# bqZUM_MCU.net
KiCad netlist of a schematic drawn in Altium Designer
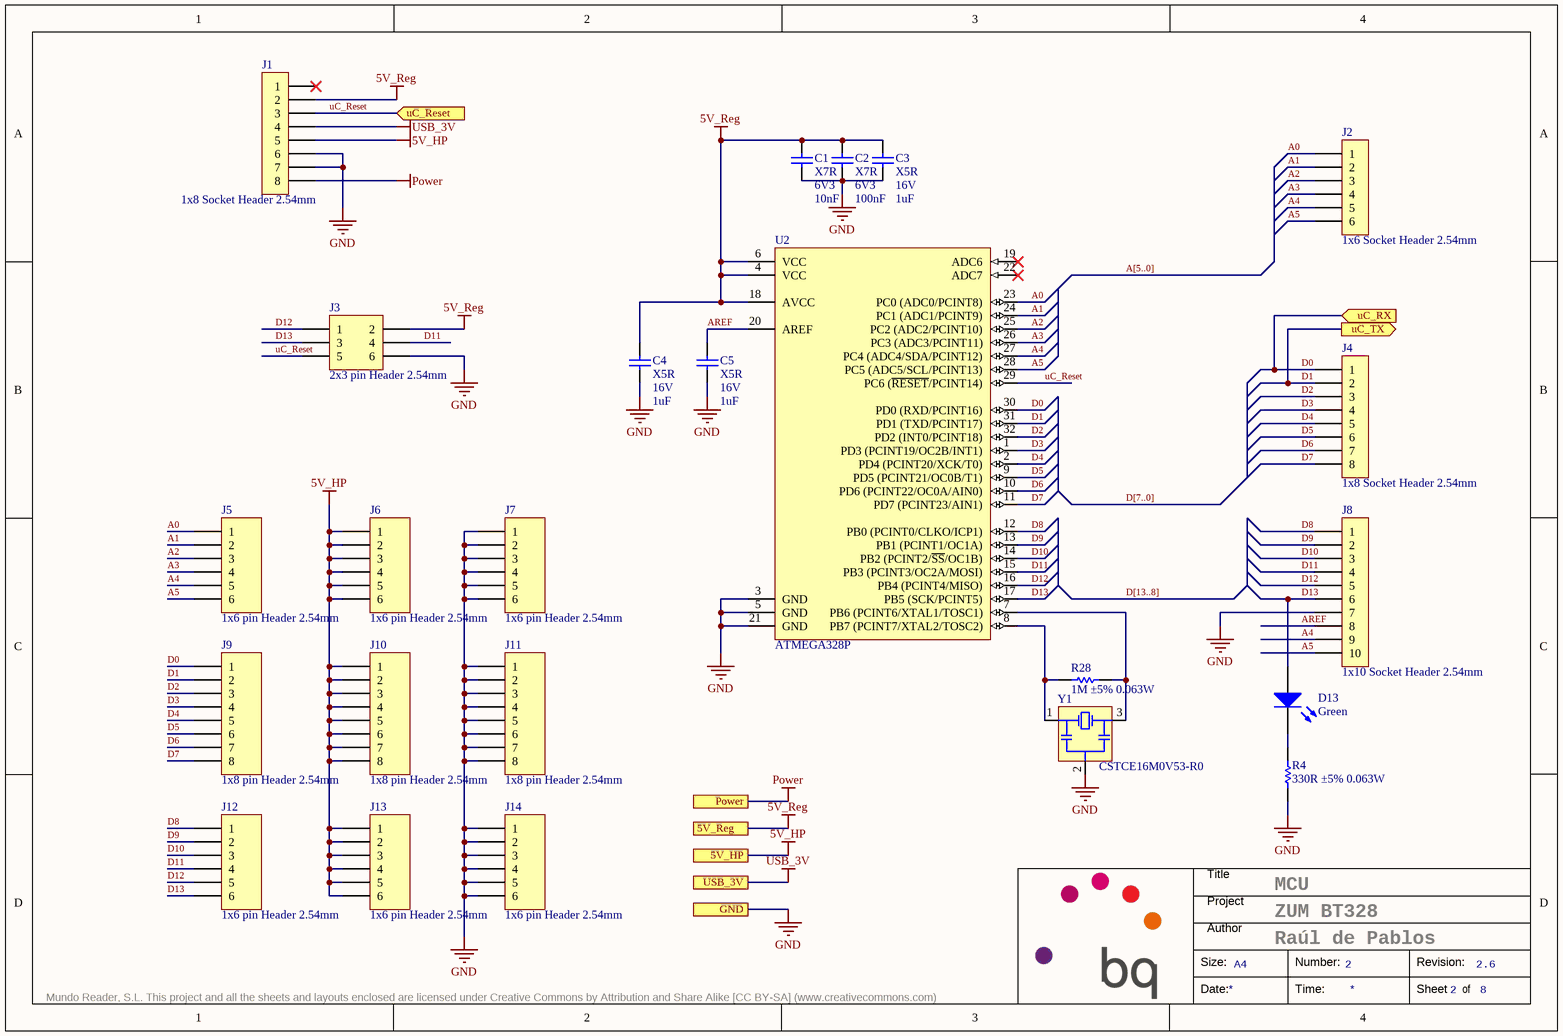
[diagram p0: bqZUM_MCU.SchDoc]

(export (version "E")
  (design (tool "Eeschema 10.0.6"))
  (components
    (comp (ref "C1")
      (value "Capacitor")
      (footprint "C0402")
      (fields
        (field (name "DIELECTRIC") "X7R")
        (field (name "VOLTAGE") "6V3")
        (field (name "CAPACITANCE") "10nF")
        (field (name "PART NUMBER") "C0402_10nF_6V3_±10%")
        (field (name "TOLERANCE") "±10%")
        (field (name "MANUFACTURER") "Kemet")
      )
      (libsource (lib "Pasives_Capacitor_SMD") (part "Capacitor"))
    )
    (comp (ref "C2")
      (value "Capacitor")
      (footprint "C0402")
      (fields
        (field (name "DIELECTRIC") "X7R")
        (field (name "VOLTAGE") "6V3")
        (field (name "CAPACITANCE") "100nF")
        (field (name "PART NUMBER") "C0402_100nF_6V3_±10%")
        (field (name "TOLERANCE") "±10%")
        (field (name "MANUFACTURER") "Kemet")
      )
      (libsource (lib "Pasives_Capacitor_SMD") (part "Capacitor"))
    )
    (comp (ref "C3")
      (value "Capacitor")
      (footprint "C0603")
      (fields
        (field (name "DIELECTRIC") "X5R")
        (field (name "VOLTAGE") "16V")
        (field (name "CAPACITANCE") "1uF")
        (field (name "PART NUMBER") "C0603_1uF_16V_±10%")
        (field (name "TOLERANCE") "±10%")
        (field (name "MANUFACTURER") "Kemet")
      )
      (libsource (lib "Pasives_Capacitor_SMD") (part "Capacitor"))
    )
    (comp (ref "C4")
      (value "Capacitor")
      (footprint "C0603")
      (fields
        (field (name "DIELECTRIC") "X5R")
        (field (name "VOLTAGE") "16V")
        (field (name "CAPACITANCE") "1uF")
        (field (name "PART NUMBER") "C0603_1uF_16V_±10%")
        (field (name "TOLERANCE") "±10%")
        (field (name "MANUFACTURER") "Kemet")
      )
      (libsource (lib "Pasives_Capacitor_SMD") (part "Capacitor"))
    )
    (comp (ref "C5")
      (value "Capacitor")
      (footprint "C0603")
      (fields
        (field (name "DIELECTRIC") "X5R")
        (field (name "VOLTAGE") "16V")
        (field (name "CAPACITANCE") "1uF")
        (field (name "PART NUMBER") "C0603_1uF_16V_±10%")
        (field (name "TOLERANCE") "±10%")
        (field (name "MANUFACTURER") "Kemet")
      )
      (libsource (lib "Pasives_Capacitor_SMD") (part "Capacitor"))
    )
    (comp (ref "D13")
      (value "Green")
      (footprint "LED0603")
      (description "Light Emitting Diode")
      (fields (field (name "PART NUMBER") "LG Q971-KN-1") (field (name "MANUFACTURER") "OSRAM Opto"))
      (libsource (lib "Optoelectronics") (part "LED"))
    )
    (comp (ref "J1")
      (value "1x8 Socket Header 2.54mm")
      (footprint "1x8 Socket Header THT 2.54mm")
      (description "8 pin Socket Header 2.54mm")
      (fields (field (name "MANUFACTURER") "Samtec") (field (name "PART NUMBER") "CON_SH_THT2.54_8"))
      (libsource (lib "Conectores_SocketHeader_2.54") (part "1x8 Socket Header 2.54mm"))
    )
    (comp (ref "J2")
      (value "1x6 Socket Header 2.54mm")
      (footprint "1x6 Socket Header THT 2.54mm")
      (description "6 pin Socket Header 2.54mm")
      (fields (field (name "MANUFACTURER") "Samtec") (field (name "PART NUMBER") "CON_SH_THT2.54_6"))
      (libsource (lib "Conectores_SocketHeader_2.54") (part "1x6 Socket Header 2.54mm"))
    )
    (comp (ref "J3")
      (value "2x3 pin Header 2.54mm")
      (footprint "2x3 Pin Header 2.54")
      (description "6 pin Dual Header 2.54mm")
      (fields (field (name "MANUFACTURER") "Samtec") (field (name "PART NUMBER") "CON_DPH_THT2.54_6"))
      (libsource (lib "Conectores_PinHeader_2.54") (part "2x3 pin Header 2.54mm"))
    )
    (comp (ref "J4")
      (value "1x8 Socket Header 2.54mm")
      (footprint "1x8 Socket Header THT 2.54mm")
      (description "8 pin Socket Header 2.54mm")
      (fields (field (name "MANUFACTURER") "Samtec") (field (name "PART NUMBER") "CON_SH_THT2.54_8"))
      (libsource (lib "") (part "1x8 Socket Header 2.54mm_1"))
    )
    (comp (ref "J5")
      (value "1x6 pin Header 2.54mm")
      (footprint "1x6 Pin Header 2.54")
      (fields (field (name "MANUFACTURER") "Samtec") (field (name "PART NUMBER") "CON_PH_THT2.54_6 Blue"))
      (libsource (lib "Conectores_PinHeader_2.54") (part "1x6 pin Header 2.54mm"))
    )
    (comp (ref "J6")
      (value "1x6 pin Header 2.54mm")
      (footprint "1x6 Pin Header 2.54")
      (fields (field (name "MANUFACTURER") "Samtec") (field (name "PART NUMBER") "CON_PH_THT2.54_6 Red"))
      (libsource (lib "Conectores_PinHeader_2.54") (part "1x6 pin Header 2.54mm"))
    )
    (comp (ref "J7")
      (value "1x6 pin Header 2.54mm")
      (footprint "1x6 Pin Header 2.54")
      (fields (field (name "MANUFACTURER") "Samtec") (field (name "PART NUMBER") "CON_PH_THT2.54_6"))
      (libsource (lib "Conectores_PinHeader_2.54") (part "1x6 pin Header 2.54mm"))
    )
    (comp (ref "J8")
      (value "1x10 Socket Header 2.54mm")
      (footprint "1x10 Socket Header THT 2.54mm")
      (description "Connector, 10 pin Socket Header 2.54mm")
      (fields (field (name "MANUFACTURER") "Samtec") (field (name "PART NUMBER") "CON_SH_THT2.54_10"))
      (libsource (lib "Conectores_SocketHeader_2.54") (part "1x10 Socket Header 2.54mm"))
    )
    (comp (ref "J9")
      (value "1x8 pin Header 2.54mm")
      (footprint "1x8 Pin Header 2.54")
      (fields (field (name "MANUFACTURER") "Samtec") (field (name "PART NUMBER") "CON_PH_THT2.54_8 Natural"))
      (libsource (lib "Conectores_PinHeader_2.54") (part "1x8 pin Header 2.54mm"))
    )
    (comp (ref "J10")
      (value "1x8 pin Header 2.54mm")
      (footprint "1x8 Pin Header 2.54")
      (fields (field (name "MANUFACTURER") "Samtec") (field (name "PART NUMBER") "CON_PH_THT2.54_8 Red"))
      (libsource (lib "Conectores_PinHeader_2.54") (part "1x8 pin Header 2.54mm"))
    )
    (comp (ref "J11")
      (value "1x8 pin Header 2.54mm")
      (footprint "1x8 Pin Header 2.54")
      (fields (field (name "MANUFACTURER") "Samtec") (field (name "PART NUMBER") "CON_PH_THT2.54_8"))
      (libsource (lib "Conectores_PinHeader_2.54") (part "1x8 pin Header 2.54mm"))
    )
    (comp (ref "J12")
      (value "1x6 pin Header 2.54mm")
      (footprint "1x6 Pin Header 2.54")
      (fields (field (name "MANUFACTURER") "Samtec") (field (name "PART NUMBER") "CON_PH_THT2.54_6 Natural"))
      (libsource (lib "Conectores_PinHeader_2.54") (part "1x6 pin Header 2.54mm"))
    )
    (comp (ref "J13")
      (value "1x6 pin Header 2.54mm")
      (footprint "1x6 Pin Header 2.54")
      (fields (field (name "MANUFACTURER") "Samtec") (field (name "PART NUMBER") "CON_PH_THT2.54_6 Red"))
      (libsource (lib "Conectores_PinHeader_2.54") (part "1x6 pin Header 2.54mm"))
    )
    (comp (ref "J14")
      (value "1x6 pin Header 2.54mm")
      (footprint "1x6 Pin Header 2.54")
      (fields (field (name "MANUFACTURER") "Samtec") (field (name "PART NUMBER") "CON_PH_THT2.54_6"))
      (libsource (lib "Conectores_PinHeader_2.54") (part "1x6 pin Header 2.54mm"))
    )
    (comp (ref "R4")
      (value "330R ±5% 0.063W")
      (footprint "R0402")
      (description "Resistor")
      (fields (field (name "TOLERANCE") "±5%") (field (name "POWER") "0.063W"))
      (libsource (lib "Pasives_Resistor_SMD") (part "Resistor"))
    )
    (comp (ref "R28")
      (value "1M ±5% 0.063W")
      (footprint "R0402")
      (description "Resistor")
      (fields (field (name "TOLERANCE") "±5%") (field (name "POWER") "0.063W"))
      (libsource (lib "Pasives_Resistor_SMD") (part "Resistor"))
    )
    (comp (ref "U2")
      (value "ATMEGA328P")
      (footprint "TQFP32")
      (description "8-bit AVR Microcontroller")
      (fields (field (name "MANUFACTURER") "Atmel"))
      (libsource (lib "Processor") (part "ATMEGA328P"))
    )
    (comp (ref "Y1")
      (value "CSTCE16M0V53-R0")
      (footprint "Resonator_1.3x3.2")
      (description "Resonator 3 pin")
      (fields (field (name "MANUFACTURER") "Murata"))
      (libsource (lib "Frequency") (part "Resonator 3 pin"))
    )
  )
  (nets
    (net (code "1") (name "/A0") (class "Default")
      (node (ref "J2") (pin "1") (pinfunction "1_1") (pintype "passive"))
      (node (ref "J5") (pin "1") (pinfunction "1_1") (pintype "passive"))
      (node (ref "U2") (pin "23") (pinfunction "PC0_(ADC0/PCINT8)_23") (pintype "bidirectional"))
    )
    (net (code "2") (name "/A1") (class "Default")
      (node (ref "J2") (pin "2") (pinfunction "2_2") (pintype "passive"))
      (node (ref "J5") (pin "2") (pinfunction "2_2") (pintype "passive"))
      (node (ref "U2") (pin "24") (pinfunction "PC1_(ADC1/PCINT9)_24") (pintype "bidirectional"))
    )
    (net (code "3") (name "/A2") (class "Default")
      (node (ref "J2") (pin "3") (pinfunction "3_3") (pintype "passive"))
      (node (ref "J5") (pin "3") (pinfunction "3_3") (pintype "passive"))
      (node (ref "U2") (pin "25") (pinfunction "PC2_(ADC2/PCINT10)_25") (pintype "bidirectional"))
    )
    (net (code "4") (name "/A3") (class "Default")
      (node (ref "J2") (pin "4") (pinfunction "4_4") (pintype "passive"))
      (node (ref "J5") (pin "4") (pinfunction "4_4") (pintype "passive"))
      (node (ref "U2") (pin "26") (pinfunction "PC3_(ADC3/PCINT11)_26") (pintype "bidirectional"))
    )
    (net (code "5") (name "/A4") (class "Default")
      (node (ref "J2") (pin "5") (pinfunction "5_5") (pintype "passive"))
      (node (ref "J5") (pin "5") (pinfunction "5_5") (pintype "passive"))
      (node (ref "J8") (pin "9") (pinfunction "9_9") (pintype "passive"))
      (node (ref "U2") (pin "27") (pinfunction "PC4_(ADC4/SDA/PCINT12)_27") (pintype "bidirectional"))
    )
    (net (code "6") (name "/A5") (class "Default")
      (node (ref "J2") (pin "6") (pinfunction "6_6") (pintype "passive"))
      (node (ref "J5") (pin "6") (pinfunction "6_6") (pintype "passive"))
      (node (ref "J8") (pin "10") (pinfunction "10_10") (pintype "passive"))
      (node (ref "U2") (pin "28") (pinfunction "PC5_(ADC5/SCL/PCINT13)_28") (pintype "bidirectional"))
    )
    (net (code "7") (name "/AREF") (class "Default")
      (node (ref "C5") (pin "2") (pinfunction "2_2") (pintype "passive"))
      (node (ref "J8") (pin "8") (pinfunction "8_8") (pintype "passive"))
      (node (ref "U2") (pin "20") (pinfunction "AREF_20") (pintype "passive"))
    )
    (net (code "9") (name "/D0") (class "Default")
      (node (ref "J4") (pin "1") (pinfunction "1_1") (pintype "passive"))
      (node (ref "J9") (pin "1") (pinfunction "1_1") (pintype "passive"))
      (node (ref "U2") (pin "30") (pinfunction "PD0_(RXD/PCINT16)_30") (pintype "bidirectional"))
    )
    (net (code "10") (name "/D1") (class "Default")
      (node (ref "J4") (pin "2") (pinfunction "2_2") (pintype "passive"))
      (node (ref "J9") (pin "2") (pinfunction "2_2") (pintype "passive"))
      (node (ref "U2") (pin "31") (pinfunction "PD1_(TXD/PCINT17)_31") (pintype "bidirectional"))
    )
    (net (code "11") (name "/D2") (class "Default")
      (node (ref "J4") (pin "3") (pinfunction "3_3") (pintype "passive"))
      (node (ref "J9") (pin "3") (pinfunction "3_3") (pintype "passive"))
      (node (ref "U2") (pin "32") (pinfunction "PD2_(INT0/PCINT18)_32") (pintype "bidirectional"))
    )
    (net (code "12") (name "/D3") (class "Default")
      (node (ref "J4") (pin "4") (pinfunction "4_4") (pintype "passive"))
      (node (ref "J9") (pin "4") (pinfunction "4_4") (pintype "passive"))
      (node (ref "U2") (pin "1") (pinfunction "PD3_(PCINT19/OC2B/INT1)_1") (pintype "bidirectional"))
    )
    (net (code "13") (name "/D4") (class "Default")
      (node (ref "J4") (pin "5") (pinfunction "5_5") (pintype "passive"))
      (node (ref "J9") (pin "5") (pinfunction "5_5") (pintype "passive"))
      (node (ref "U2") (pin "2") (pinfunction "PD4_(PCINT20/XCK/T0)_2") (pintype "bidirectional"))
    )
    (net (code "14") (name "/D5") (class "Default")
      (node (ref "J4") (pin "6") (pinfunction "6_6") (pintype "passive"))
      (node (ref "J9") (pin "6") (pinfunction "6_6") (pintype "passive"))
      (node (ref "U2") (pin "9") (pinfunction "PD5_(PCINT21/OC0B/T1)_9") (pintype "bidirectional"))
    )
    (net (code "15") (name "/D6") (class "Default")
      (node (ref "J4") (pin "7") (pinfunction "7_7") (pintype "passive"))
      (node (ref "J9") (pin "7") (pinfunction "7_7") (pintype "passive"))
      (node (ref "U2") (pin "10") (pinfunction "PD6_(PCINT22/OC0A/AIN0)_10") (pintype "bidirectional"))
    )
    (net (code "16") (name "/D7") (class "Default")
      (node (ref "J4") (pin "8") (pinfunction "8_8") (pintype "passive"))
      (node (ref "J9") (pin "8") (pinfunction "8_8") (pintype "passive"))
      (node (ref "U2") (pin "11") (pinfunction "PD7_(PCINT23/AIN1)_11") (pintype "bidirectional"))
    )
    (net (code "17") (name "/D8") (class "Default")
      (node (ref "J12") (pin "1") (pinfunction "1_1") (pintype "passive"))
      (node (ref "J8") (pin "1") (pinfunction "1_1") (pintype "passive"))
      (node (ref "U2") (pin "12") (pinfunction "PB0_(PCINT0/CLKO/ICP1)_12") (pintype "bidirectional"))
    )
    (net (code "18") (name "/D9") (class "Default")
      (node (ref "J12") (pin "2") (pinfunction "2_2") (pintype "passive"))
      (node (ref "J8") (pin "2") (pinfunction "2_2") (pintype "passive"))
      (node (ref "U2") (pin "13") (pinfunction "PB1_(PCINT1/OC1A)_13") (pintype "bidirectional"))
    )
    (net (code "19") (name "/D10") (class "Default")
      (node (ref "J12") (pin "3") (pinfunction "3_3") (pintype "passive"))
      (node (ref "J8") (pin "3") (pinfunction "3_3") (pintype "passive"))
      (node (ref "U2") (pin "14") (pinfunction "PB2_(PCINT2/~{SS}/OC1B)_14") (pintype "bidirectional"))
    )
    (net (code "20") (name "/D11") (class "Default")
      (node (ref "J12") (pin "4") (pinfunction "4_4") (pintype "passive"))
      (node (ref "J3") (pin "4") (pinfunction "4_4") (pintype "passive"))
      (node (ref "J8") (pin "4") (pinfunction "4_4") (pintype "passive"))
      (node (ref "U2") (pin "15") (pinfunction "PB3_(PCINT3/OC2A/MOSI)_15") (pintype "bidirectional"))
    )
    (net (code "21") (name "/D12") (class "Default")
      (node (ref "J12") (pin "5") (pinfunction "5_5") (pintype "passive"))
      (node (ref "J3") (pin "1") (pinfunction "1_1") (pintype "passive"))
      (node (ref "J8") (pin "5") (pinfunction "5_5") (pintype "passive"))
      (node (ref "U2") (pin "16") (pinfunction "PB4_(PCINT4/MISO)_16") (pintype "bidirectional"))
    )
    (net (code "22") (name "/D13") (class "Default")
      (node (ref "D13") (pin "A") (pinfunction "A_A") (pintype "passive"))
      (node (ref "J12") (pin "6") (pinfunction "6_6") (pintype "passive"))
      (node (ref "J3") (pin "3") (pinfunction "3_3") (pintype "passive"))
      (node (ref "J8") (pin "6") (pinfunction "6_6") (pintype "passive"))
      (node (ref "U2") (pin "17") (pinfunction "PB5_(SCK/PCINT5)_17") (pintype "bidirectional"))
    )
    (net (code "25") (name "/uC_Reset") (class "Default")
      (node (ref "J1") (pin "3") (pinfunction "3_3") (pintype "passive"))
      (node (ref "J3") (pin "5") (pinfunction "5_5") (pintype "passive"))
      (node (ref "U2") (pin "29") (pinfunction "PC6_(~{RESET}/PCINT14)_29") (pintype "bidirectional"))
    )
    (net (code "26") (name "5V_HP") (class "Default")
      (node (ref "J1") (pin "5") (pinfunction "5_5") (pintype "passive"))
      (node (ref "J10") (pin "1") (pinfunction "1_1") (pintype "passive"))
      (node (ref "J10") (pin "2") (pinfunction "2_2") (pintype "passive"))
      (node (ref "J10") (pin "3") (pinfunction "3_3") (pintype "passive"))
      (node (ref "J10") (pin "4") (pinfunction "4_4") (pintype "passive"))
      (node (ref "J10") (pin "5") (pinfunction "5_5") (pintype "passive"))
      (node (ref "J10") (pin "6") (pinfunction "6_6") (pintype "passive"))
      (node (ref "J10") (pin "7") (pinfunction "7_7") (pintype "passive"))
      (node (ref "J10") (pin "8") (pinfunction "8_8") (pintype "passive"))
      (node (ref "J13") (pin "1") (pinfunction "1_1") (pintype "passive"))
      (node (ref "J13") (pin "2") (pinfunction "2_2") (pintype "passive"))
      (node (ref "J13") (pin "3") (pinfunction "3_3") (pintype "passive"))
      (node (ref "J13") (pin "4") (pinfunction "4_4") (pintype "passive"))
      (node (ref "J13") (pin "5") (pinfunction "5_5") (pintype "passive"))
      (node (ref "J13") (pin "6") (pinfunction "6_6") (pintype "passive"))
      (node (ref "J6") (pin "1") (pinfunction "1_1") (pintype "passive"))
      (node (ref "J6") (pin "2") (pinfunction "2_2") (pintype "passive"))
      (node (ref "J6") (pin "3") (pinfunction "3_3") (pintype "passive"))
      (node (ref "J6") (pin "4") (pinfunction "4_4") (pintype "passive"))
      (node (ref "J6") (pin "5") (pinfunction "5_5") (pintype "passive"))
      (node (ref "J6") (pin "6") (pinfunction "6_6") (pintype "passive"))
    )
    (net (code "27") (name "5V_Reg") (class "Default")
      (node (ref "C1") (pin "2") (pinfunction "2_2") (pintype "passive"))
      (node (ref "C2") (pin "2") (pinfunction "2_2") (pintype "passive"))
      (node (ref "C3") (pin "2") (pinfunction "2_2") (pintype "passive"))
      (node (ref "C4") (pin "2") (pinfunction "2_2") (pintype "passive"))
      (node (ref "J1") (pin "2") (pinfunction "2_2") (pintype "passive"))
      (node (ref "J3") (pin "2") (pinfunction "2_2") (pintype "passive"))
      (node (ref "U2") (pin "18") (pinfunction "AVCC_18") (pintype "power_in"))
      (node (ref "U2") (pin "4") (pinfunction "VCC_4") (pintype "power_in"))
      (node (ref "U2") (pin "6") (pinfunction "VCC_6") (pintype "power_in"))
    )
    (net (code "28") (name "GND") (class "Default")
      (node (ref "C1") (pin "1") (pinfunction "1_1") (pintype "passive"))
      (node (ref "C2") (pin "1") (pinfunction "1_1") (pintype "passive"))
      (node (ref "C3") (pin "1") (pinfunction "1_1") (pintype "passive"))
      (node (ref "C4") (pin "1") (pinfunction "1_1") (pintype "passive"))
      (node (ref "C5") (pin "1") (pinfunction "1_1") (pintype "passive"))
      (node (ref "J1") (pin "6") (pinfunction "6_6") (pintype "passive"))
      (node (ref "J1") (pin "7") (pinfunction "7_7") (pintype "passive"))
      (node (ref "J11") (pin "1") (pinfunction "1_1") (pintype "passive"))
      (node (ref "J11") (pin "2") (pinfunction "2_2") (pintype "passive"))
      (node (ref "J11") (pin "3") (pinfunction "3_3") (pintype "passive"))
      (node (ref "J11") (pin "4") (pinfunction "4_4") (pintype "passive"))
      (node (ref "J11") (pin "5") (pinfunction "5_5") (pintype "passive"))
      (node (ref "J11") (pin "6") (pinfunction "6_6") (pintype "passive"))
      (node (ref "J11") (pin "7") (pinfunction "7_7") (pintype "passive"))
      (node (ref "J11") (pin "8") (pinfunction "8_8") (pintype "passive"))
      (node (ref "J14") (pin "1") (pinfunction "1_1") (pintype "passive"))
      (node (ref "J14") (pin "2") (pinfunction "2_2") (pintype "passive"))
      (node (ref "J14") (pin "3") (pinfunction "3_3") (pintype "passive"))
      (node (ref "J14") (pin "4") (pinfunction "4_4") (pintype "passive"))
      (node (ref "J14") (pin "5") (pinfunction "5_5") (pintype "passive"))
      (node (ref "J14") (pin "6") (pinfunction "6_6") (pintype "passive"))
      (node (ref "J3") (pin "6") (pinfunction "6_6") (pintype "passive"))
      (node (ref "J7") (pin "1") (pinfunction "1_1") (pintype "passive"))
      (node (ref "J7") (pin "2") (pinfunction "2_2") (pintype "passive"))
      (node (ref "J7") (pin "3") (pinfunction "3_3") (pintype "passive"))
      (node (ref "J7") (pin "4") (pinfunction "4_4") (pintype "passive"))
      (node (ref "J7") (pin "5") (pinfunction "5_5") (pintype "passive"))
      (node (ref "J7") (pin "6") (pinfunction "6_6") (pintype "passive"))
      (node (ref "J8") (pin "7") (pinfunction "7_7") (pintype "passive"))
      (node (ref "R4") (pin "1") (pinfunction "1_1") (pintype "passive"))
      (node (ref "U2") (pin "21") (pinfunction "GND_21") (pintype "power_in"))
      (node (ref "U2") (pin "3") (pinfunction "GND_3") (pintype "power_in"))
      (node (ref "U2") (pin "5") (pinfunction "GND_5") (pintype "power_in"))
      (node (ref "Y1") (pin "2") (pinfunction "GND_2") (pintype "passive"))
    )
    (net (code "29") (name "Net-(D13-PadK)") (class "Default")
      (node (ref "D13") (pin "K") (pinfunction "K_K") (pintype "passive"))
      (node (ref "R4") (pin "2") (pinfunction "2_2") (pintype "passive"))
    )
    (net (code "30") (name "Net-(U2-PB6_(PCINT6{slash}XTAL1{slash}TOSC1))") (class "Default")
      (node (ref "R28") (pin "2") (pinfunction "2_2") (pintype "passive"))
      (node (ref "U2") (pin "7") (pinfunction "PB6_(PCINT6/XTAL1/TOSC1)_7") (pintype "bidirectional"))
      (node (ref "Y1") (pin "3") (pinfunction "OSC2_3") (pintype "passive"))
    )
    (net (code "31") (name "Net-(U2-PB7_(PCINT7{slash}XTAL2{slash}TOSC2))") (class "Default")
      (node (ref "R28") (pin "1") (pinfunction "1_1") (pintype "passive"))
      (node (ref "U2") (pin "8") (pinfunction "PB7_(PCINT7/XTAL2/TOSC2)_8") (pintype "bidirectional"))
      (node (ref "Y1") (pin "1") (pinfunction "OSC1_1") (pintype "passive"))
    )
    (net (code "32") (name "Power") (class "Default")
      (node (ref "J1") (pin "8") (pinfunction "8_8") (pintype "passive"))
    )
    (net (code "33") (name "USB_3V") (class "Default")
      (node (ref "J1") (pin "4") (pinfunction "4_4") (pintype "passive"))
    )
    (net (code "34") (name "unconnected-(J1-Pad1)") (class "Default")
      (node (ref "J1") (pin "1") (pinfunction "1_1") (pintype "passive+no_connect"))
    )
    (net (code "35") (name "unconnected-(U2-ADC6-Pad19)") (class "Default")
      (node (ref "U2") (pin "19") (pinfunction "ADC6_19") (pintype "input+no_connect"))
    )
    (net (code "36") (name "unconnected-(U2-ADC7-Pad22)") (class "Default")
      (node (ref "U2") (pin "22") (pinfunction "ADC7_22") (pintype "input+no_connect"))
    )
  )
)
